# MCU.net
KiCad netlist of a schematic drawn in Altium Designer
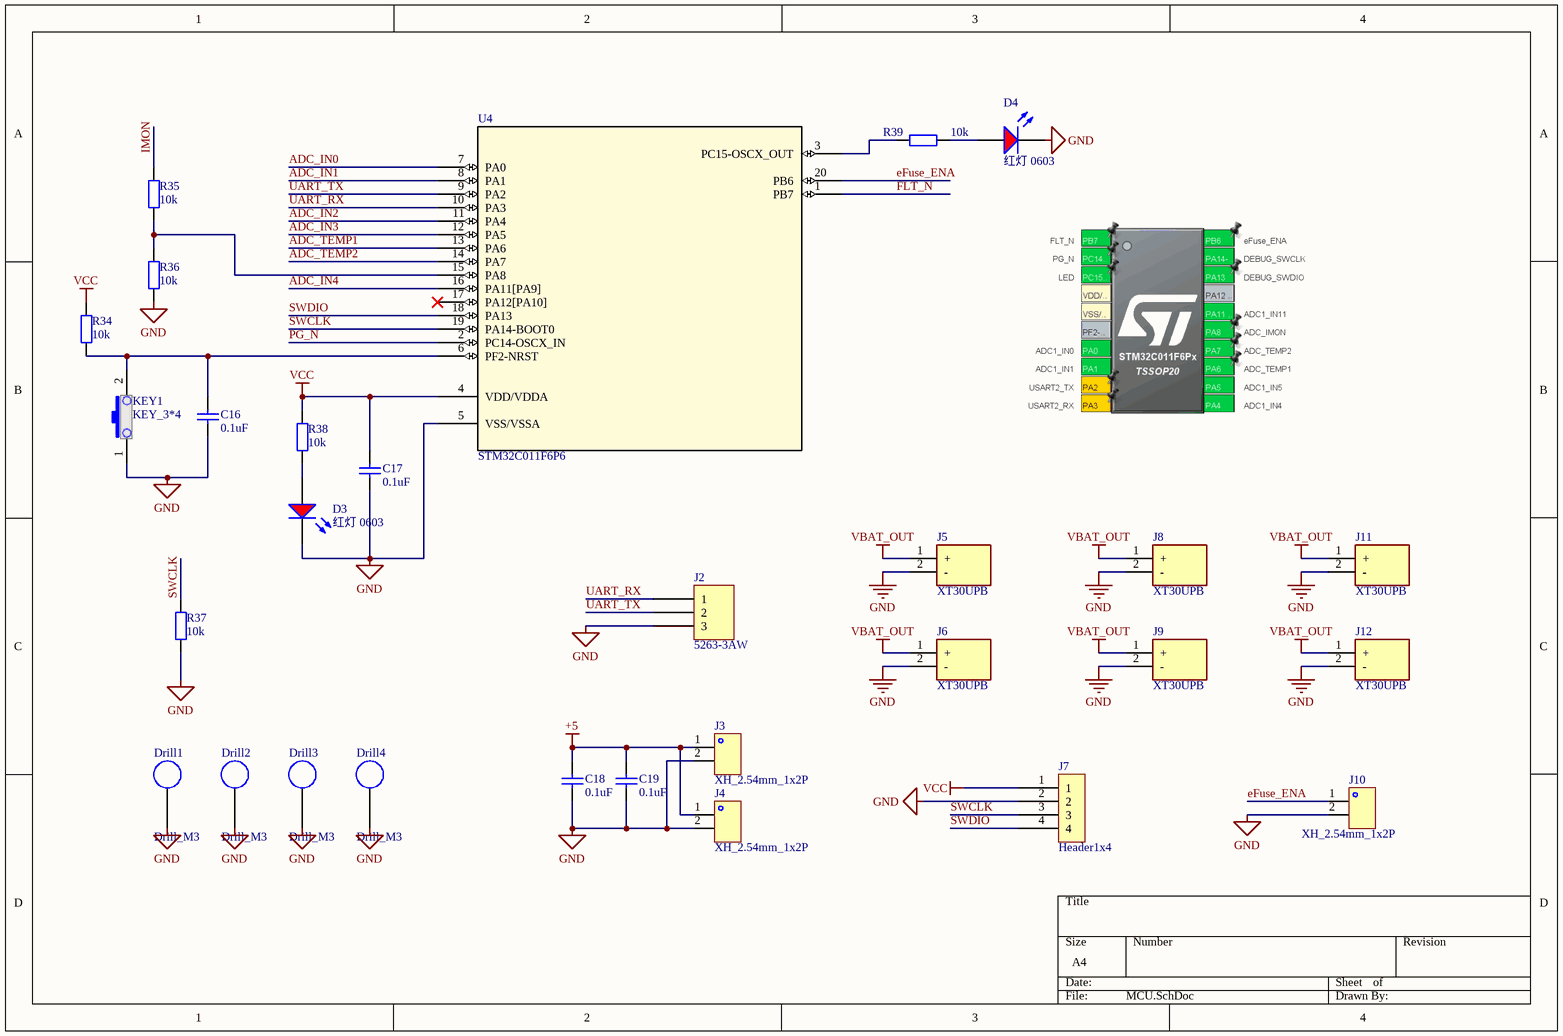
[diagram p0: MCU.SchDoc]

(export (version "E")
  (design (tool "Eeschema 10.0.6"))
  (components
    (comp (ref "C16") (value "0.1uF") (footprint "C0603") (libsource (lib "NetTie") (part "Capacitor")))
    (comp (ref "C17") (value "0.1uF") (footprint "C0603") (libsource (lib "NetTie") (part "Capacitor")))
    (comp (ref "C18") (value "0.1uF") (footprint "C0603") (libsource (lib "NetTie") (part "Capacitor")))
    (comp (ref "C19") (value "0.1uF") (footprint "C0603") (libsource (lib "NetTie") (part "Capacitor")))
    (comp (ref "D3")
      (value "红灯 0603")
      (footprint "0603_LED_S1")
      (description "发光二极管")
      (libsource (lib "LED") (part "0603 红灯"))
    )
    (comp (ref "D4")
      (value "红灯 0603")
      (footprint "0603_LED_S1")
      (description "发光二极管")
      (libsource (lib "LED") (part "0603 红灯"))
    )
    (comp (ref "Drill1")
      (value "Drill_M3")
      (footprint "Drill_M_3")
      (libsource (lib "NetTie") (part "Drill_M3"))
    )
    (comp (ref "Drill2")
      (value "Drill_M3")
      (footprint "Drill_M_3")
      (libsource (lib "NetTie") (part "Drill_M3"))
    )
    (comp (ref "Drill3")
      (value "Drill_M3")
      (footprint "Drill_M_3")
      (libsource (lib "NetTie") (part "Drill_M3"))
    )
    (comp (ref "Drill4")
      (value "Drill_M3")
      (footprint "Drill_M_3")
      (libsource (lib "NetTie") (part "Drill_M3"))
    )
    (comp (ref "J2")
      (value "5263-3AW")
      (footprint "5264-3AW")
      (libsource (lib "Connectors") (part "5263-3AW"))
    )
    (comp (ref "J3")
      (value "XH_2.54mm_1x2P")
      (footprint "XH2.54mm1x2P弯插")
      (libsource (lib "NetTie") (part "XH_2.54mm_1x2P"))
    )
    (comp (ref "J4")
      (value "XH_2.54mm_1x2P")
      (footprint "XH2.54mm1x2P弯插")
      (libsource (lib "NetTie") (part "XH_2.54mm_1x2P"))
    )
    (comp (ref "J5") (value "XT30UPB") (footprint "XT30UPB") (libsource (lib "Connectors") (part "XT30UPB")))
    (comp (ref "J6") (value "XT30UPB") (footprint "XT30UPB") (libsource (lib "Connectors") (part "XT30UPB")))
    (comp (ref "J7")
      (value "Header1x4")
      (footprint "Header 1x4p")
      (libsource (lib "Connectors") (part "Header1x4"))
    )
    (comp (ref "J8") (value "XT30UPB") (footprint "XT30UPB") (libsource (lib "Connectors") (part "XT30UPB")))
    (comp (ref "J9") (value "XT30UPB") (footprint "XT30UPB") (libsource (lib "Connectors") (part "XT30UPB")))
    (comp (ref "J10")
      (value "XH_2.54mm_1x2P")
      (footprint "XH2.54mm1x2P弯插")
      (libsource (lib "NetTie") (part "XH_2.54mm_1x2P"))
    )
    (comp (ref "J11") (value "XT30UPB") (footprint "XT30UPB") (libsource (lib "Connectors") (part "XT30UPB")))
    (comp (ref "J12") (value "XT30UPB") (footprint "XT30UPB") (libsource (lib "Connectors") (part "XT30UPB")))
    (comp (ref "KEY1")
      (value "KEY_3*4")
      (footprint "KEY_3*4")
      (description "C707339")
      (libsource (lib "NetTie") (part "KEY_3*4"))
    )
    (comp (ref "R34") (value "10k") (footprint "R0603") (libsource (lib "NetTie") (part "Resistor")))
    (comp (ref "R35") (value "10k") (footprint "R0603") (libsource (lib "NetTie") (part "Resistor")))
    (comp (ref "R36") (value "10k") (footprint "R0603") (libsource (lib "NetTie") (part "Resistor")))
    (comp (ref "R37") (value "10k") (footprint "R0603") (libsource (lib "NetTie") (part "Resistor")))
    (comp (ref "R38") (value "10k") (footprint "R0603") (libsource (lib "") (part "Resistor_2")))
    (comp (ref "R39") (value "10k") (footprint "R0603") (libsource (lib "") (part "Resistor_1")))
    (comp (ref "U4")
      (value "STM32C011F6P6")
      (footprint "TSSOP20_STM")
      (description "No Description Available")
      (fields (field (name "COPYRIGHT") "Copyright (C) 2024 Ultra Librarian. All rights reserved."))
      (libsource (lib "CommonUsedComponents") (part "STM32C011F6P6"))
    )
  )
  (nets
    (net (code "1") (name "+5") (class "Default")
      (node (ref "C18") (pin "1") (pinfunction "1_1") (pintype "passive"))
      (node (ref "C19") (pin "1") (pinfunction "1_1") (pintype "passive"))
      (node (ref "J3") (pin "1") (pinfunction "1_1") (pintype "passive"))
      (node (ref "J4") (pin "1") (pinfunction "1_1") (pintype "passive"))
    )
    (net (code "2") (name "/ADC_IN0") (class "Default")
      (node (ref "U4") (pin "7") (pinfunction "PA0_7") (pintype "bidirectional"))
    )
    (net (code "3") (name "/ADC_IN1") (class "Default")
      (node (ref "U4") (pin "8") (pinfunction "PA1_8") (pintype "bidirectional"))
    )
    (net (code "4") (name "/ADC_IN2") (class "Default")
      (node (ref "U4") (pin "11") (pinfunction "PA4_11") (pintype "bidirectional"))
    )
    (net (code "5") (name "/ADC_IN3") (class "Default")
      (node (ref "U4") (pin "12") (pinfunction "PA5_12") (pintype "bidirectional"))
    )
    (net (code "6") (name "/ADC_IN4") (class "Default")
      (node (ref "U4") (pin "16") (pinfunction "PA11[PA9]_16") (pintype "bidirectional"))
    )
    (net (code "7") (name "/ADC_TEMP1") (class "Default")
      (node (ref "U4") (pin "13") (pinfunction "PA6_13") (pintype "bidirectional"))
    )
    (net (code "8") (name "/ADC_TEMP2") (class "Default")
      (node (ref "U4") (pin "14") (pinfunction "PA7_14") (pintype "bidirectional"))
    )
    (net (code "9") (name "/FLT_N") (class "Default")
      (node (ref "U4") (pin "1") (pinfunction "PB7_1") (pintype "bidirectional"))
    )
    (net (code "10") (name "/IMON") (class "Default")
      (node (ref "R35") (pin "2") (pinfunction "2_2") (pintype "passive"))
    )
    (net (code "11") (name "/PG_N") (class "Default")
      (node (ref "U4") (pin "2") (pinfunction "PC14-OSCX_IN_2") (pintype "bidirectional"))
    )
    (net (code "12") (name "/SWCLK") (class "Default")
      (node (ref "J7") (pin "3") (pinfunction "3_3") (pintype "passive"))
      (node (ref "R37") (pin "2") (pinfunction "2_2") (pintype "passive"))
      (node (ref "U4") (pin "19") (pinfunction "PA14-BOOT0_19") (pintype "bidirectional"))
    )
    (net (code "13") (name "/SWDIO") (class "Default")
      (node (ref "J7") (pin "4") (pinfunction "4_4") (pintype "passive"))
      (node (ref "U4") (pin "18") (pinfunction "PA13_18") (pintype "bidirectional"))
    )
    (net (code "14") (name "/UART_RX") (class "Default")
      (node (ref "J2") (pin "1") (pinfunction "1_1") (pintype "passive"))
      (node (ref "U4") (pin "10") (pinfunction "PA3_10") (pintype "bidirectional"))
    )
    (net (code "15") (name "/UART_TX") (class "Default")
      (node (ref "J2") (pin "2") (pinfunction "2_2") (pintype "passive"))
      (node (ref "U4") (pin "9") (pinfunction "PA2_9") (pintype "bidirectional"))
    )
    (net (code "16") (name "/eFuse_ENA") (class "Default")
      (node (ref "J10") (pin "1") (pinfunction "1_1") (pintype "passive"))
      (node (ref "U4") (pin "20") (pinfunction "PB6_20") (pintype "bidirectional"))
    )
    (net (code "17") (name "GND") (class "Default")
      (node (ref "C16") (pin "1") (pinfunction "1_1") (pintype "passive"))
      (node (ref "C17") (pin "1") (pinfunction "1_1") (pintype "passive"))
      (node (ref "C18") (pin "2") (pinfunction "2_2") (pintype "passive"))
      (node (ref "C19") (pin "2") (pinfunction "2_2") (pintype "passive"))
      (node (ref "D3") (pin "K") (pinfunction "K_K") (pintype "passive"))
      (node (ref "D4") (pin "K") (pinfunction "K_K") (pintype "passive"))
      (node (ref "Drill1") (pin "0") (pinfunction "A_0") (pintype "passive"))
      (node (ref "Drill2") (pin "0") (pinfunction "A_0") (pintype "passive"))
      (node (ref "Drill3") (pin "0") (pinfunction "A_0") (pintype "passive"))
      (node (ref "Drill4") (pin "0") (pinfunction "A_0") (pintype "passive"))
      (node (ref "J10") (pin "2") (pinfunction "2_2") (pintype "passive"))
      (node (ref "J11") (pin "2") (pinfunction "-_2") (pintype "passive"))
      (node (ref "J12") (pin "2") (pinfunction "-_2") (pintype "passive"))
      (node (ref "J2") (pin "3") (pinfunction "3_3") (pintype "passive"))
      (node (ref "J3") (pin "2") (pinfunction "2_2") (pintype "passive"))
      (node (ref "J4") (pin "2") (pinfunction "2_2") (pintype "passive"))
      (node (ref "J5") (pin "2") (pinfunction "-_2") (pintype "passive"))
      (node (ref "J6") (pin "2") (pinfunction "-_2") (pintype "passive"))
      (node (ref "J7") (pin "2") (pinfunction "2_2") (pintype "passive"))
      (node (ref "J8") (pin "2") (pinfunction "-_2") (pintype "passive"))
      (node (ref "J9") (pin "2") (pinfunction "-_2") (pintype "passive"))
      (node (ref "KEY1") (pin "1") (pinfunction "1_1") (pintype "passive"))
      (node (ref "R36") (pin "1") (pinfunction "1_1") (pintype "passive"))
      (node (ref "R37") (pin "1") (pinfunction "1_1") (pintype "passive"))
      (node (ref "U4") (pin "5") (pinfunction "VSS/VSSA_5") (pintype "power_in"))
    )
    (net (code "18") (name "Net-(D3-PadA)") (class "Default")
      (node (ref "D3") (pin "A") (pinfunction "A_A") (pintype "passive"))
      (node (ref "R38") (pin "2") (pinfunction "2_2") (pintype "passive"))
    )
    (net (code "19") (name "Net-(D4-PadA)") (class "Default")
      (node (ref "D4") (pin "A") (pinfunction "A_A") (pintype "passive"))
      (node (ref "R39") (pin "2") (pinfunction "2_2") (pintype "passive"))
    )
    (net (code "20") (name "Net-(U4-PA8)") (class "Default")
      (node (ref "R35") (pin "1") (pinfunction "1_1") (pintype "passive"))
      (node (ref "R36") (pin "2") (pinfunction "2_2") (pintype "passive"))
      (node (ref "U4") (pin "15") (pinfunction "PA8_15") (pintype "bidirectional"))
    )
    (net (code "21") (name "Net-(U4-PC15-OSCX_OUT)") (class "Default")
      (node (ref "R39") (pin "1") (pinfunction "1_1") (pintype "passive"))
      (node (ref "U4") (pin "3") (pinfunction "PC15-OSCX_OUT_3") (pintype "bidirectional"))
    )
    (net (code "22") (name "Net-(U4-PF2-NRST)") (class "Default")
      (node (ref "C16") (pin "2") (pinfunction "2_2") (pintype "passive"))
      (node (ref "KEY1") (pin "2") (pinfunction "2_2") (pintype "passive"))
      (node (ref "R34") (pin "1") (pinfunction "1_1") (pintype "passive"))
      (node (ref "U4") (pin "6") (pinfunction "PF2-NRST_6") (pintype "bidirectional"))
    )
    (net (code "23") (name "VBAT_OUT") (class "Default")
      (node (ref "J11") (pin "1") (pinfunction "+_1") (pintype "passive"))
      (node (ref "J12") (pin "1") (pinfunction "+_1") (pintype "passive"))
      (node (ref "J5") (pin "1") (pinfunction "+_1") (pintype "passive"))
      (node (ref "J6") (pin "1") (pinfunction "+_1") (pintype "passive"))
      (node (ref "J8") (pin "1") (pinfunction "+_1") (pintype "passive"))
      (node (ref "J9") (pin "1") (pinfunction "+_1") (pintype "passive"))
    )
    (net (code "24") (name "VCC") (class "Default")
      (node (ref "C17") (pin "2") (pinfunction "2_2") (pintype "passive"))
      (node (ref "J7") (pin "1") (pinfunction "1_1") (pintype "passive"))
      (node (ref "R34") (pin "2") (pinfunction "2_2") (pintype "passive"))
      (node (ref "R38") (pin "1") (pinfunction "1_1") (pintype "passive"))
      (node (ref "U4") (pin "4") (pinfunction "VDD/VDDA_4") (pintype "power_in"))
    )
    (net (code "25") (name "unconnected-(U4-PA12[PA10]-Pad17)") (class "Default")
      (node (ref "U4") (pin "17") (pinfunction "PA12[PA10]_17") (pintype "bidirectional+no_connect"))
    )
  )
)
